# MainController.net
KiCad netlist of a schematic drawn in EAGLE
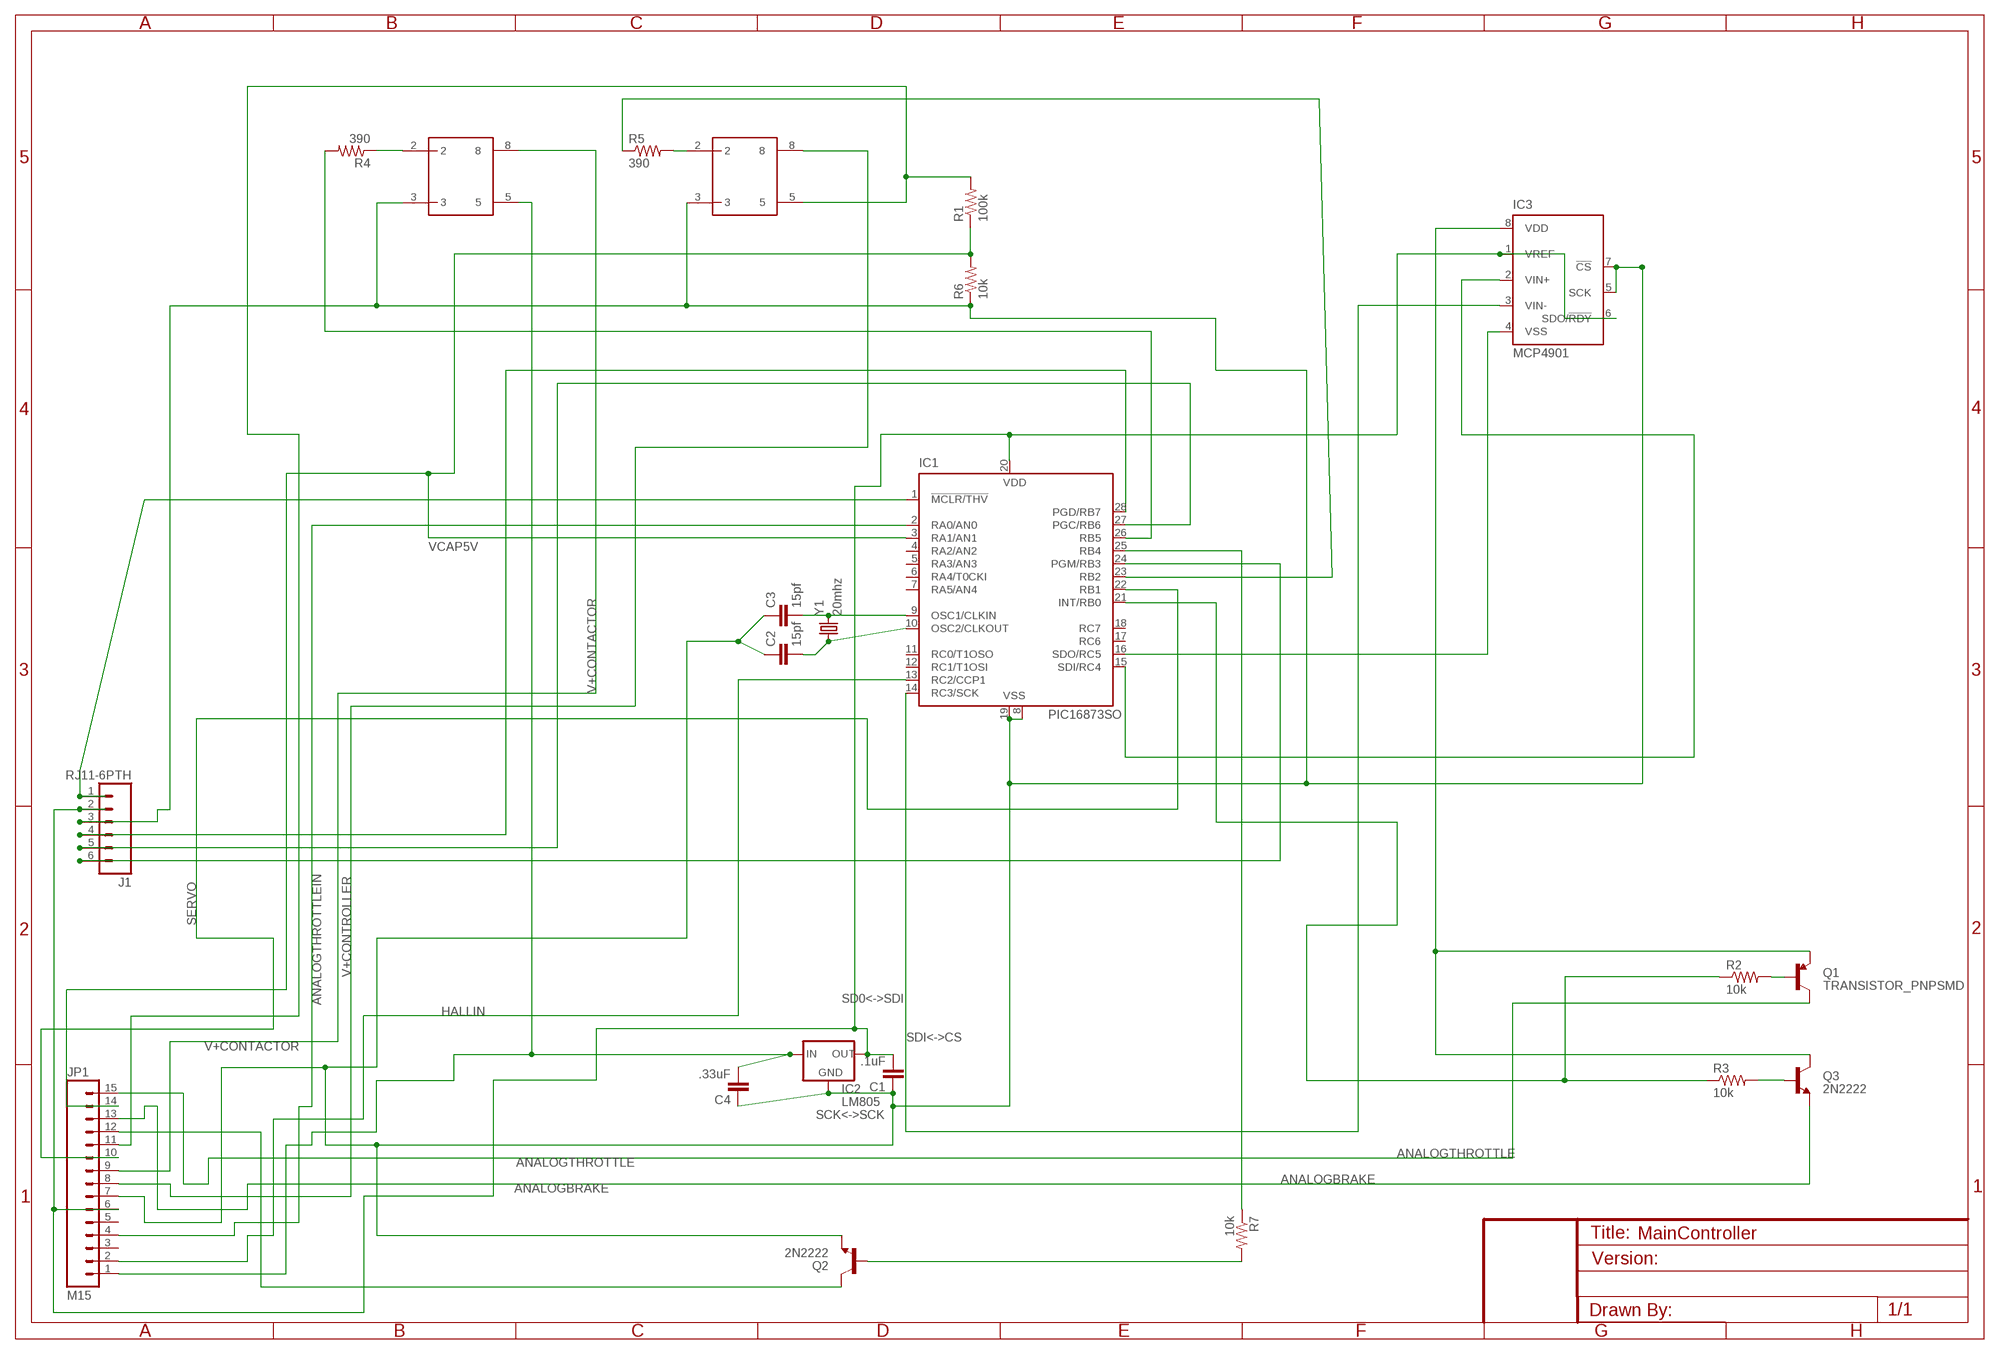
[diagram p0: schematic, sheet 1]

(export (version "E")
  (design (tool "Eeschema 10.0.6"))
  (components
    (comp (ref "C1")
      (value ".1uF")
      (footprint "eagle-import:0402-CAP")
      (libsource (lib "eagle-import") (part "CAP0402-CAP"))
    )
    (comp (ref "C2")
      (value "15pf")
      (footprint "eagle-import:0402-CAP")
      (libsource (lib "eagle-import") (part "CAP0402-CAP"))
    )
    (comp (ref "C3")
      (value "15pf")
      (footprint "eagle-import:0402-CAP")
      (libsource (lib "eagle-import") (part "CAP0402-CAP"))
    )
    (comp (ref "C4")
      (value ".33uF")
      (footprint "eagle-import:0402-CAP")
      (libsource (lib "eagle-import") (part "CAP0402-CAP"))
    )
    (comp (ref "IC1")
      (value "PIC16873SO")
      (footprint "eagle-import:SO28W")
      (libsource (lib "eagle-import") (part "PIC16873SO"))
    )
    (comp (ref "IC2")
      (value "LM805")
      (footprint "eagle-import:78XXL")
      (libsource (lib "eagle-import") (part "78XXL"))
    )
    (comp (ref "IC3")
      (value "MCP4901")
      (footprint "eagle-import:SO-08")
      (fields (field (name "MF") "MICROCHIP") (field (name "MPN") "MCP3553-E/SN"))
      (libsource (lib "eagle-import") (part "MCP355SN3"))
    )
    (comp (ref "J1")
      (value "RJ11-6PTH")
      (footprint "eagle-import:RJ11-6")
      (libsource (lib "eagle-import") (part "RJ11-6PTH"))
    )
    (comp (ref "JP1")
      (value "M15")
      (footprint "eagle-import:1X15")
      (libsource (lib "eagle-import") (part "M15"))
    )
    (comp (ref "Q1")
      (value "TRANSISTOR_PNPSMD")
      (footprint "eagle-import:SOT23-3")
      (libsource (lib "eagle-import") (part "TRANSISTOR_PNPSMD"))
    )
    (comp (ref "Q2")
      (value "2N2222")
      (footprint "eagle-import:SOT23-3")
      (libsource (lib "eagle-import") (part "TRANSISTOR_NPNSOT23-3"))
    )
    (comp (ref "Q3")
      (value "2N2222")
      (footprint "eagle-import:SOT23")
      (libsource (lib "eagle-import") (part "TRANSISTOR_NPNSOT23"))
    )
    (comp (ref "R1")
      (value "100k")
      (footprint "eagle-import:0805")
      (libsource (lib "eagle-import") (part "RESISTOR0805-RES"))
    )
    (comp (ref "R2")
      (value "10k")
      (footprint "eagle-import:0805")
      (libsource (lib "eagle-import") (part "RESISTOR0805-RES"))
    )
    (comp (ref "R3")
      (value "10k")
      (footprint "eagle-import:0805")
      (libsource (lib "eagle-import") (part "RESISTOR0805-RES"))
    )
    (comp (ref "R4")
      (value "390")
      (footprint "eagle-import:0805")
      (libsource (lib "eagle-import") (part "RESISTOR0805-RES"))
    )
    (comp (ref "R5")
      (value "390")
      (footprint "eagle-import:0805")
      (libsource (lib "eagle-import") (part "RESISTOR0805-RES"))
    )
    (comp (ref "R6")
      (value "10k")
      (footprint "eagle-import:0805")
      (libsource (lib "eagle-import") (part "RESISTOR0805-RES"))
    )
    (comp (ref "R7")
      (value "10k")
      (footprint "eagle-import:0805")
      (libsource (lib "eagle-import") (part "RESISTOR0805-RES"))
    )
    (comp (ref "U$14")
      (value "OPTO_DARL_6N138S")
      (footprint "eagle-import:8-SMD")
      (libsource (lib "eagle-import") (part "OPTO_DARL_6N138S"))
    )
    (comp (ref "U$18")
      (value "OPTO_DARL_6N138S")
      (footprint "eagle-import:8-SMD")
      (libsource (lib "eagle-import") (part "OPTO_DARL_6N138S"))
    )
    (comp (ref "Y1")
      (value "20mhz")
      (footprint "eagle-import:HC49US")
      (libsource (lib "eagle-import") (part "CRYSTALHC49US"))
    )
  )
  (nets
    (net (code "1") (name "/ANALOGBRAKE") (class "Default")
      (node (ref "JP1") (pin "13") (pinfunction "13_13") (pintype "passive"))
      (node (ref "Q3") (pin "2") (pinfunction "E_2") (pintype "passive"))
    )
    (net (code "2") (name "/ANALOGTHROTTLE") (class "Default")
      (node (ref "JP1") (pin "15") (pinfunction "15_15") (pintype "passive"))
      (node (ref "Q1") (pin "3") (pinfunction "C_3") (pintype "passive"))
    )
    (net (code "3") (name "/ANALOGTHROTTLEIN") (class "Default")
      (node (ref "IC1") (pin "2") (pinfunction "RA0/AN0_2") (pintype "bidirectional"))
      (node (ref "JP1") (pin "4") (pinfunction "4_4") (pintype "passive"))
    )
    (net (code "4") (name "/HALLIN") (class "Default")
      (node (ref "IC1") (pin "13") (pinfunction "RC2/CCP1_13") (pintype "bidirectional"))
      (node (ref "JP1") (pin "2") (pinfunction "2_2") (pintype "passive"))
    )
    (net (code "5") (name "/SCK<->SCK") (class "Default")
      (node (ref "IC1") (pin "14") (pinfunction "RC3/SCK_14") (pintype "bidirectional"))
      (node (ref "IC3") (pin "3") (pinfunction "VIN-_3") (pintype "input"))
    )
    (net (code "6") (name "/SD0<->SDI") (class "Default")
      (node (ref "IC1") (pin "16") (pinfunction "SDO/RC5_16") (pintype "bidirectional"))
      (node (ref "IC3") (pin "4") (pinfunction "VSS_4") (pintype "power_in"))
    )
    (net (code "7") (name "/SDI<->CS") (class "Default")
      (node (ref "IC1") (pin "15") (pinfunction "SDI/RC4_15") (pintype "bidirectional"))
      (node (ref "IC3") (pin "2") (pinfunction "VIN+_2") (pintype "input"))
    )
    (net (code "8") (name "/SERVO") (class "Default")
      (node (ref "IC1") (pin "22") (pinfunction "RB1_22") (pintype "bidirectional"))
      (node (ref "JP1") (pin "10") (pinfunction "10_10") (pintype "passive"))
    )
    (net (code "9") (name "/V+CONTACTOR") (class "Default")
      (node (ref "JP1") (pin "9") (pinfunction "9_9") (pintype "passive"))
      (node (ref "U$14") (pin "8") (pinfunction "8_8") (pintype "bidirectional"))
    )
    (net (code "10") (name "/V+CONTROLLER") (class "Default")
      (node (ref "JP1") (pin "8") (pinfunction "8_8") (pintype "passive"))
      (node (ref "U$18") (pin "8") (pinfunction "8_8") (pintype "bidirectional"))
    )
    (net (code "11") (name "/VCAP5V") (class "Default")
      (node (ref "IC1") (pin "3") (pinfunction "RA1/AN1_3") (pintype "bidirectional"))
      (node (ref "JP1") (pin "14") (pinfunction "14_14") (pintype "passive"))
      (node (ref "R1") (pin "1") (pinfunction "1_1") (pintype "passive"))
      (node (ref "R6") (pin "2") (pinfunction "2_2") (pintype "passive"))
    )
    (net (code "12") (name "Net-(C4-Pad2)") (class "Default")
      (node (ref "C4") (pin "2") (pinfunction "2_2") (pintype "passive"))
      (node (ref "IC2") (pin "IN") (pinfunction "IN_IN") (pintype "input"))
      (node (ref "JP1") (pin "1") (pinfunction "1_1") (pintype "passive"))
      (node (ref "U$14") (pin "5") (pinfunction "5_5") (pintype "bidirectional"))
    )
    (net (code "13") (name "Net-(IC1-INT{slash}RB0)") (class "Default")
      (node (ref "IC1") (pin "21") (pinfunction "INT/RB0_21") (pintype "bidirectional"))
      (node (ref "R2") (pin "1") (pinfunction "1_1") (pintype "passive"))
      (node (ref "R3") (pin "1") (pinfunction "1_1") (pintype "passive"))
    )
    (net (code "14") (name "Net-(IC1-OSC1{slash}CLKIN)") (class "Default")
      (node (ref "C3") (pin "2") (pinfunction "2_2") (pintype "passive"))
      (node (ref "IC1") (pin "9") (pinfunction "OSC1/CLKIN_9") (pintype "input"))
      (node (ref "Y1") (pin "2") (pinfunction "2_2") (pintype "passive"))
    )
    (net (code "15") (name "Net-(IC1-OSC2{slash}CLKOUT)") (class "Default")
      (node (ref "C2") (pin "2") (pinfunction "2_2") (pintype "passive"))
      (node (ref "IC1") (pin "10") (pinfunction "OSC2/CLKOUT_10") (pintype "output"))
      (node (ref "Y1") (pin "1") (pinfunction "1_1") (pintype "passive"))
    )
    (net (code "16") (name "Net-(IC1-PGC{slash}RB6)") (class "Default")
      (node (ref "IC1") (pin "27") (pinfunction "PGC/RB6_27") (pintype "bidirectional"))
      (node (ref "J1") (pin "5") (pinfunction "5_5") (pintype "passive"))
    )
    (net (code "17") (name "Net-(IC1-PGD{slash}RB7)") (class "Default")
      (node (ref "IC1") (pin "28") (pinfunction "PGD/RB7_28") (pintype "bidirectional"))
      (node (ref "J1") (pin "4") (pinfunction "4_4") (pintype "passive"))
    )
    (net (code "18") (name "Net-(IC1-PGM{slash}RB3)") (class "Default")
      (node (ref "IC1") (pin "24") (pinfunction "PGM/RB3_24") (pintype "bidirectional"))
      (node (ref "J1") (pin "6") (pinfunction "6_6") (pintype "passive"))
    )
    (net (code "19") (name "Net-(IC1-RB2)") (class "Default")
      (node (ref "IC1") (pin "23") (pinfunction "RB2_23") (pintype "bidirectional"))
      (node (ref "R5") (pin "1") (pinfunction "1_1") (pintype "passive"))
    )
    (net (code "20") (name "Net-(IC1-RB4)") (class "Default")
      (node (ref "IC1") (pin "25") (pinfunction "RB4_25") (pintype "bidirectional"))
      (node (ref "R7") (pin "1") (pinfunction "1_1") (pintype "passive"))
    )
    (net (code "21") (name "Net-(IC1-RB5)") (class "Default")
      (node (ref "IC1") (pin "26") (pinfunction "RB5_26") (pintype "bidirectional"))
      (node (ref "R4") (pin "2") (pinfunction "2_2") (pintype "passive"))
    )
    (net (code "22") (name "Net-(IC1-VDD)") (class "Default")
      (node (ref "C1") (pin "2") (pinfunction "2_2") (pintype "passive"))
      (node (ref "IC1") (pin "20") (pinfunction "VDD_20") (pintype "power_in"))
      (node (ref "IC2") (pin "OUT") (pinfunction "OUT_OUT") (pintype "passive"))
      (node (ref "IC3") (pin "1") (pinfunction "VREF_1") (pintype "input"))
      (node (ref "IC3") (pin "6") (pinfunction "SDO/~{RDY}_6") (pintype "output"))
      (node (ref "J1") (pin "2") (pinfunction "2_2") (pintype "passive"))
      (node (ref "JP1") (pin "6") (pinfunction "6_6") (pintype "passive"))
    )
    (net (code "23") (name "Net-(IC1-~{MCLR{slash}THV})") (class "Default")
      (node (ref "IC1") (pin "1") (pinfunction "~{MCLR/THV}_1") (pintype "input"))
      (node (ref "J1") (pin "1") (pinfunction "1_1") (pintype "passive"))
    )
    (net (code "24") (name "Net-(IC3-SCK)") (class "Default")
      (node (ref "C1") (pin "1") (pinfunction "1_1") (pintype "passive"))
      (node (ref "C2") (pin "1") (pinfunction "1_1") (pintype "passive"))
      (node (ref "C3") (pin "1") (pinfunction "1_1") (pintype "passive"))
      (node (ref "C4") (pin "1") (pinfunction "1_1") (pintype "passive"))
      (node (ref "IC1") (pin "19") (pinfunction "VSS_19") (pintype "power_in"))
      (node (ref "IC1") (pin "8") (pinfunction "VSS_8") (pintype "power_in"))
      (node (ref "IC2") (pin "GND") (pinfunction "GND_GND") (pintype "input"))
      (node (ref "IC3") (pin "5") (pinfunction "SCK_5") (pintype "input"))
      (node (ref "IC3") (pin "7") (pinfunction "~{CS}_7") (pintype "input"))
      (node (ref "J1") (pin "3") (pinfunction "3_3") (pintype "passive"))
      (node (ref "JP1") (pin "7") (pinfunction "7_7") (pintype "passive"))
      (node (ref "Q2") (pin "2") (pinfunction "E_2") (pintype "passive"))
      (node (ref "R6") (pin "1") (pinfunction "1_1") (pintype "passive"))
      (node (ref "U$14") (pin "3") (pinfunction "3_3") (pintype "bidirectional"))
      (node (ref "U$18") (pin "3") (pinfunction "3_3") (pintype "bidirectional"))
    )
    (net (code "25") (name "Net-(IC3-VDD)") (class "Default")
      (node (ref "IC3") (pin "8") (pinfunction "VDD_8") (pintype "power_in"))
      (node (ref "Q1") (pin "2") (pinfunction "E_2") (pintype "passive"))
      (node (ref "Q3") (pin "3") (pinfunction "C_3") (pintype "passive"))
    )
    (net (code "26") (name "Net-(JP1-Pad11)") (class "Default")
      (node (ref "JP1") (pin "11") (pinfunction "11_11") (pintype "passive"))
      (node (ref "R1") (pin "2") (pinfunction "2_2") (pintype "passive"))
      (node (ref "U$18") (pin "5") (pinfunction "5_5") (pintype "bidirectional"))
    )
    (net (code "27") (name "Net-(Q1-B)") (class "Default")
      (node (ref "Q1") (pin "1") (pinfunction "B_1") (pintype "passive"))
      (node (ref "R2") (pin "2") (pinfunction "2_2") (pintype "passive"))
    )
    (net (code "28") (name "Net-(Q2-B)") (class "Default")
      (node (ref "Q2") (pin "1") (pinfunction "B_1") (pintype "passive"))
      (node (ref "R7") (pin "2") (pinfunction "2_2") (pintype "passive"))
    )
    (net (code "29") (name "Net-(Q2-C)") (class "Default")
      (node (ref "JP1") (pin "12") (pinfunction "12_12") (pintype "passive"))
      (node (ref "Q2") (pin "3") (pinfunction "C_3") (pintype "passive"))
    )
    (net (code "30") (name "Net-(Q3-B)") (class "Default")
      (node (ref "Q3") (pin "1") (pinfunction "B_1") (pintype "passive"))
      (node (ref "R3") (pin "2") (pinfunction "2_2") (pintype "passive"))
    )
    (net (code "31") (name "Net-(R4-Pad1)") (class "Default")
      (node (ref "R4") (pin "1") (pinfunction "1_1") (pintype "passive"))
      (node (ref "U$14") (pin "2") (pinfunction "2_2") (pintype "bidirectional"))
    )
    (net (code "32") (name "Net-(R5-Pad2)") (class "Default")
      (node (ref "R5") (pin "2") (pinfunction "2_2") (pintype "passive"))
      (node (ref "U$18") (pin "2") (pinfunction "2_2") (pintype "bidirectional"))
    )
    (net (code "33") (name "unconnected-(IC1-RA2{slash}AN2-Pad4)") (class "Default")
      (node (ref "IC1") (pin "4") (pinfunction "RA2/AN2_4") (pintype "bidirectional"))
    )
    (net (code "34") (name "unconnected-(IC1-RA3{slash}AN3-Pad5)") (class "Default")
      (node (ref "IC1") (pin "5") (pinfunction "RA3/AN3_5") (pintype "bidirectional"))
    )
    (net (code "35") (name "unconnected-(IC1-RA4{slash}T0CKI-Pad6)") (class "Default")
      (node (ref "IC1") (pin "6") (pinfunction "RA4/T0CKI_6") (pintype "bidirectional"))
    )
    (net (code "36") (name "unconnected-(IC1-RA5{slash}AN4-Pad7)") (class "Default")
      (node (ref "IC1") (pin "7") (pinfunction "RA5/AN4_7") (pintype "bidirectional"))
    )
    (net (code "37") (name "unconnected-(IC1-RC0{slash}T1OSO-Pad11)") (class "Default")
      (node (ref "IC1") (pin "11") (pinfunction "RC0/T1OSO_11") (pintype "bidirectional"))
    )
    (net (code "38") (name "unconnected-(IC1-RC1{slash}T1OSI-Pad12)") (class "Default")
      (node (ref "IC1") (pin "12") (pinfunction "RC1/T1OSI_12") (pintype "bidirectional"))
    )
    (net (code "39") (name "unconnected-(IC1-RC6-Pad17)") (class "Default")
      (node (ref "IC1") (pin "17") (pinfunction "RC6_17") (pintype "bidirectional"))
    )
    (net (code "40") (name "unconnected-(IC1-RC7-Pad18)") (class "Default")
      (node (ref "IC1") (pin "18") (pinfunction "RC7_18") (pintype "bidirectional"))
    )
    (net (code "41") (name "unconnected-(JP1-Pad3)") (class "Default")
      (node (ref "JP1") (pin "3") (pinfunction "3_3") (pintype "passive"))
    )
    (net (code "42") (name "unconnected-(JP1-Pad5)") (class "Default")
      (node (ref "JP1") (pin "5") (pinfunction "5_5") (pintype "passive"))
    )
  )
)
